# Mag_Read_STM_OUT.net
KiCad netlist of a schematic drawn in EAGLE
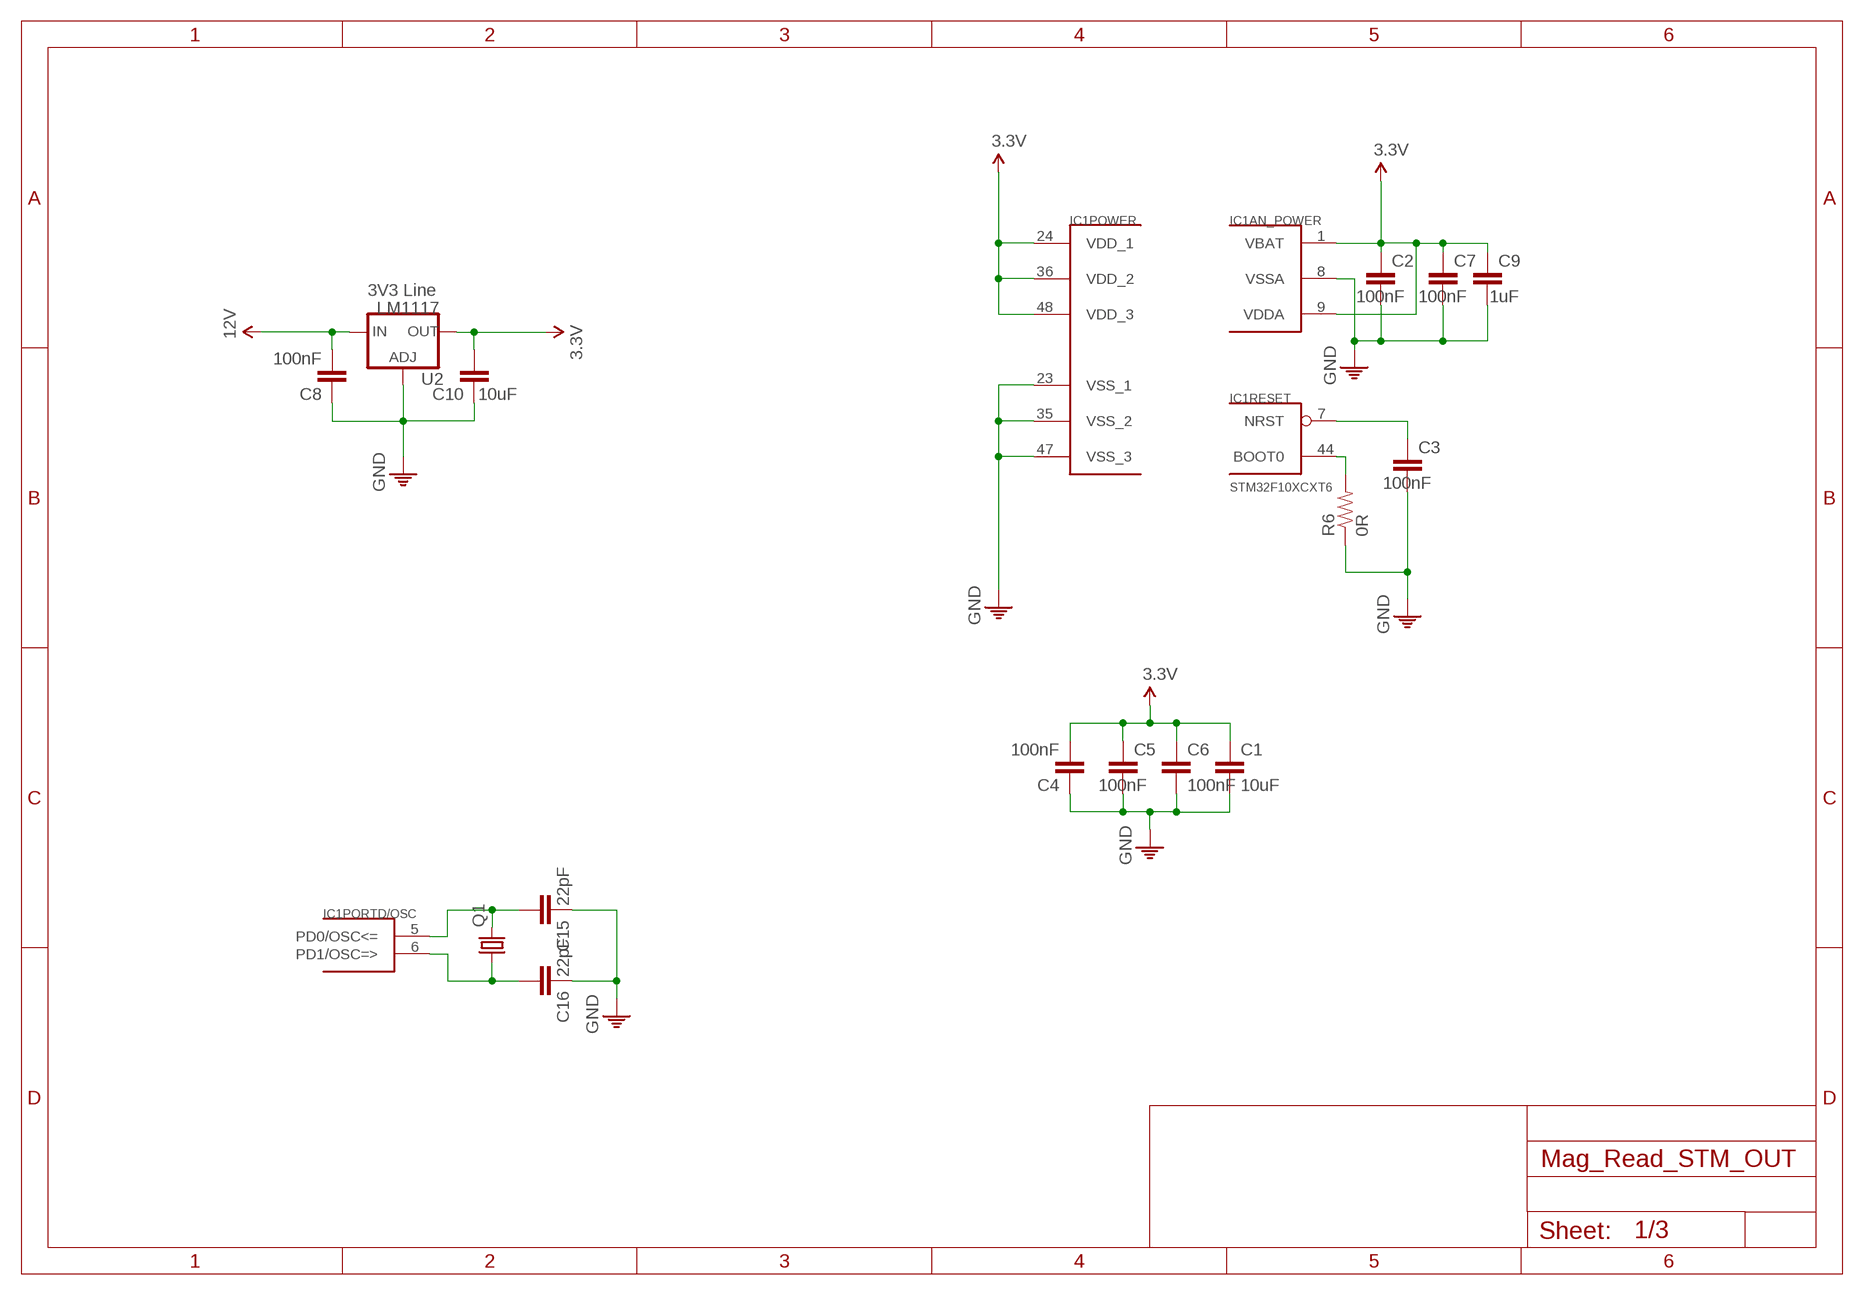
[diagram p0: schematic, sheet 1]
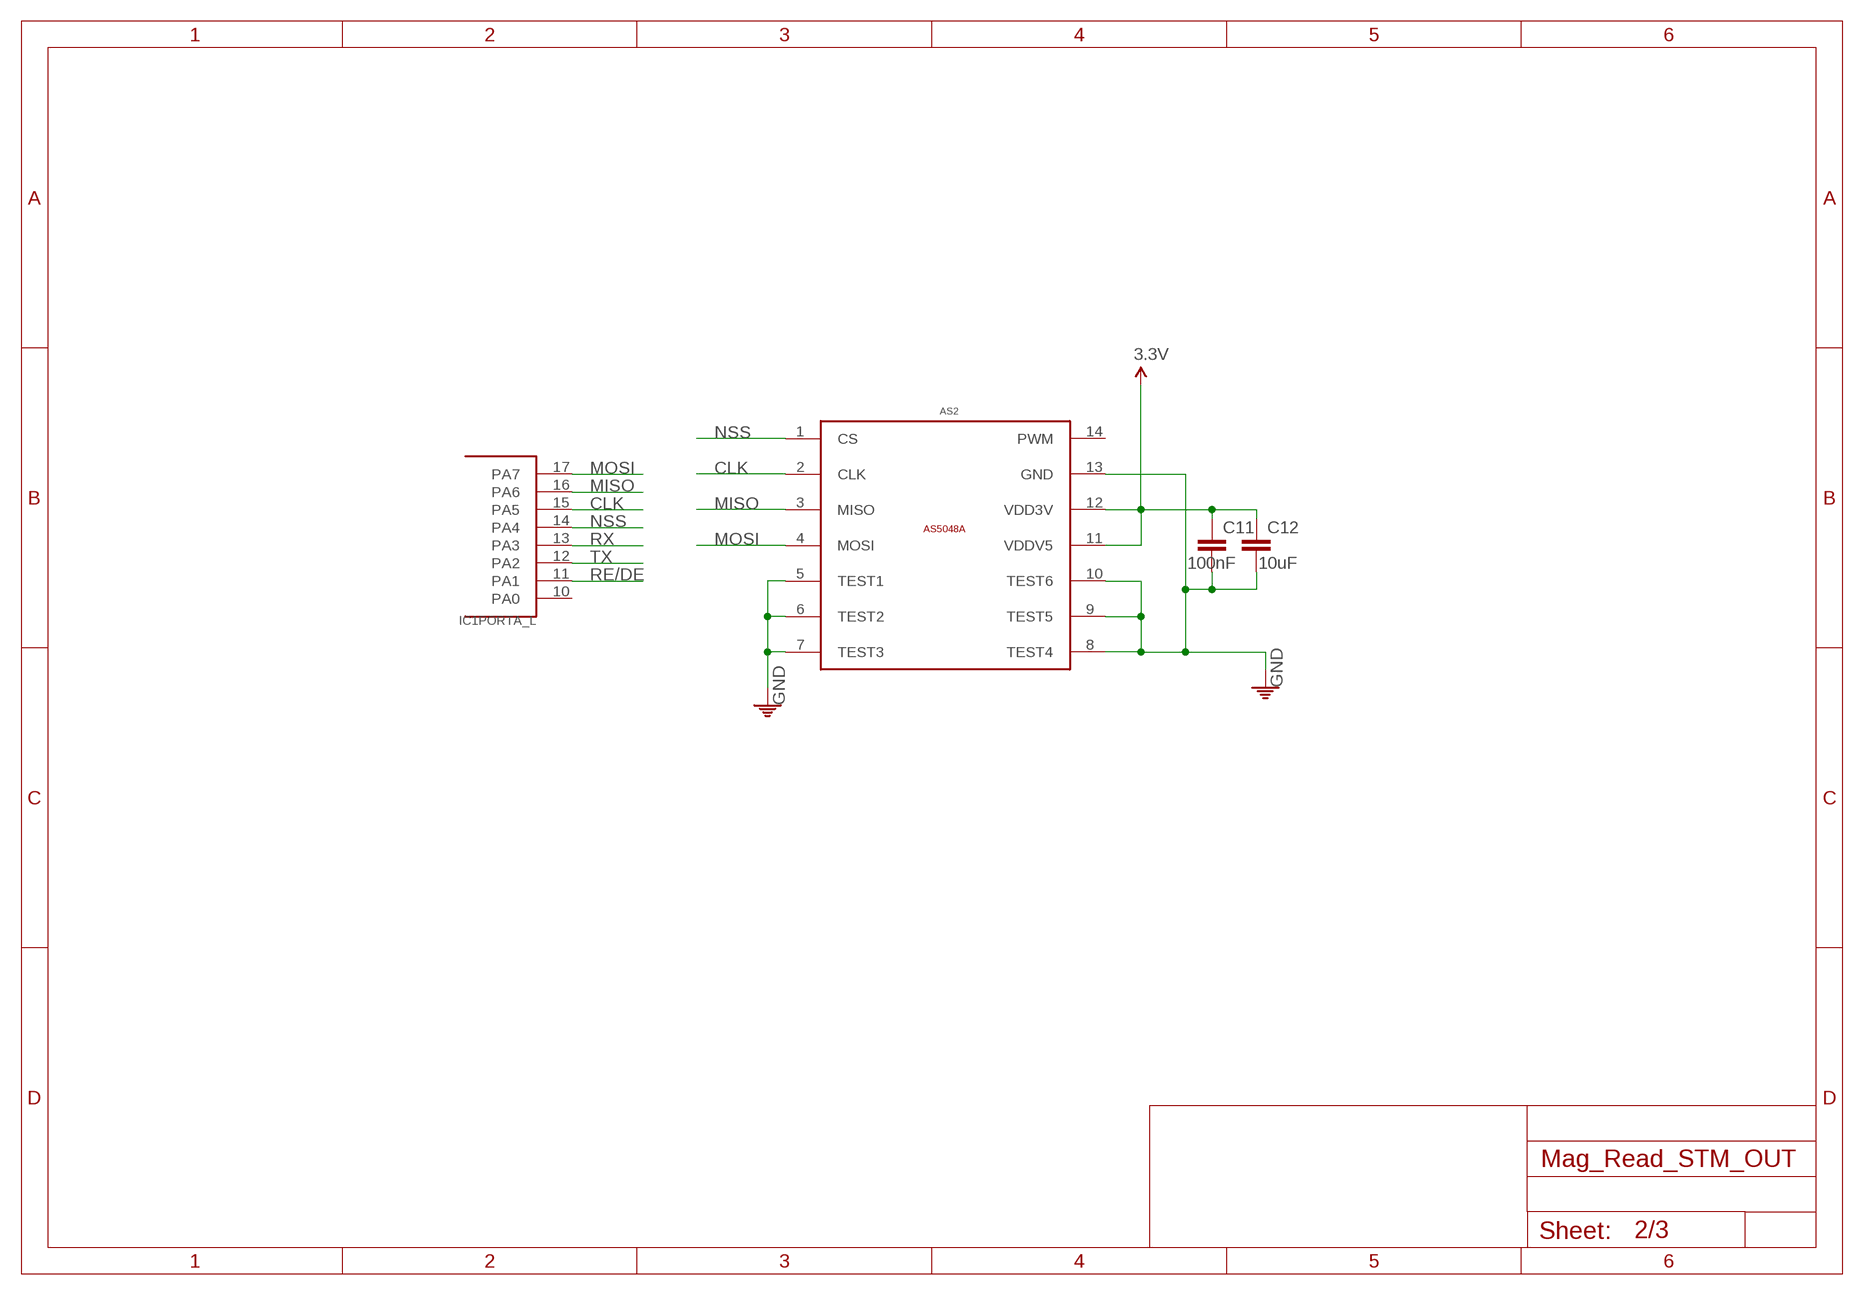
[diagram p1: schematic, sheet 2]
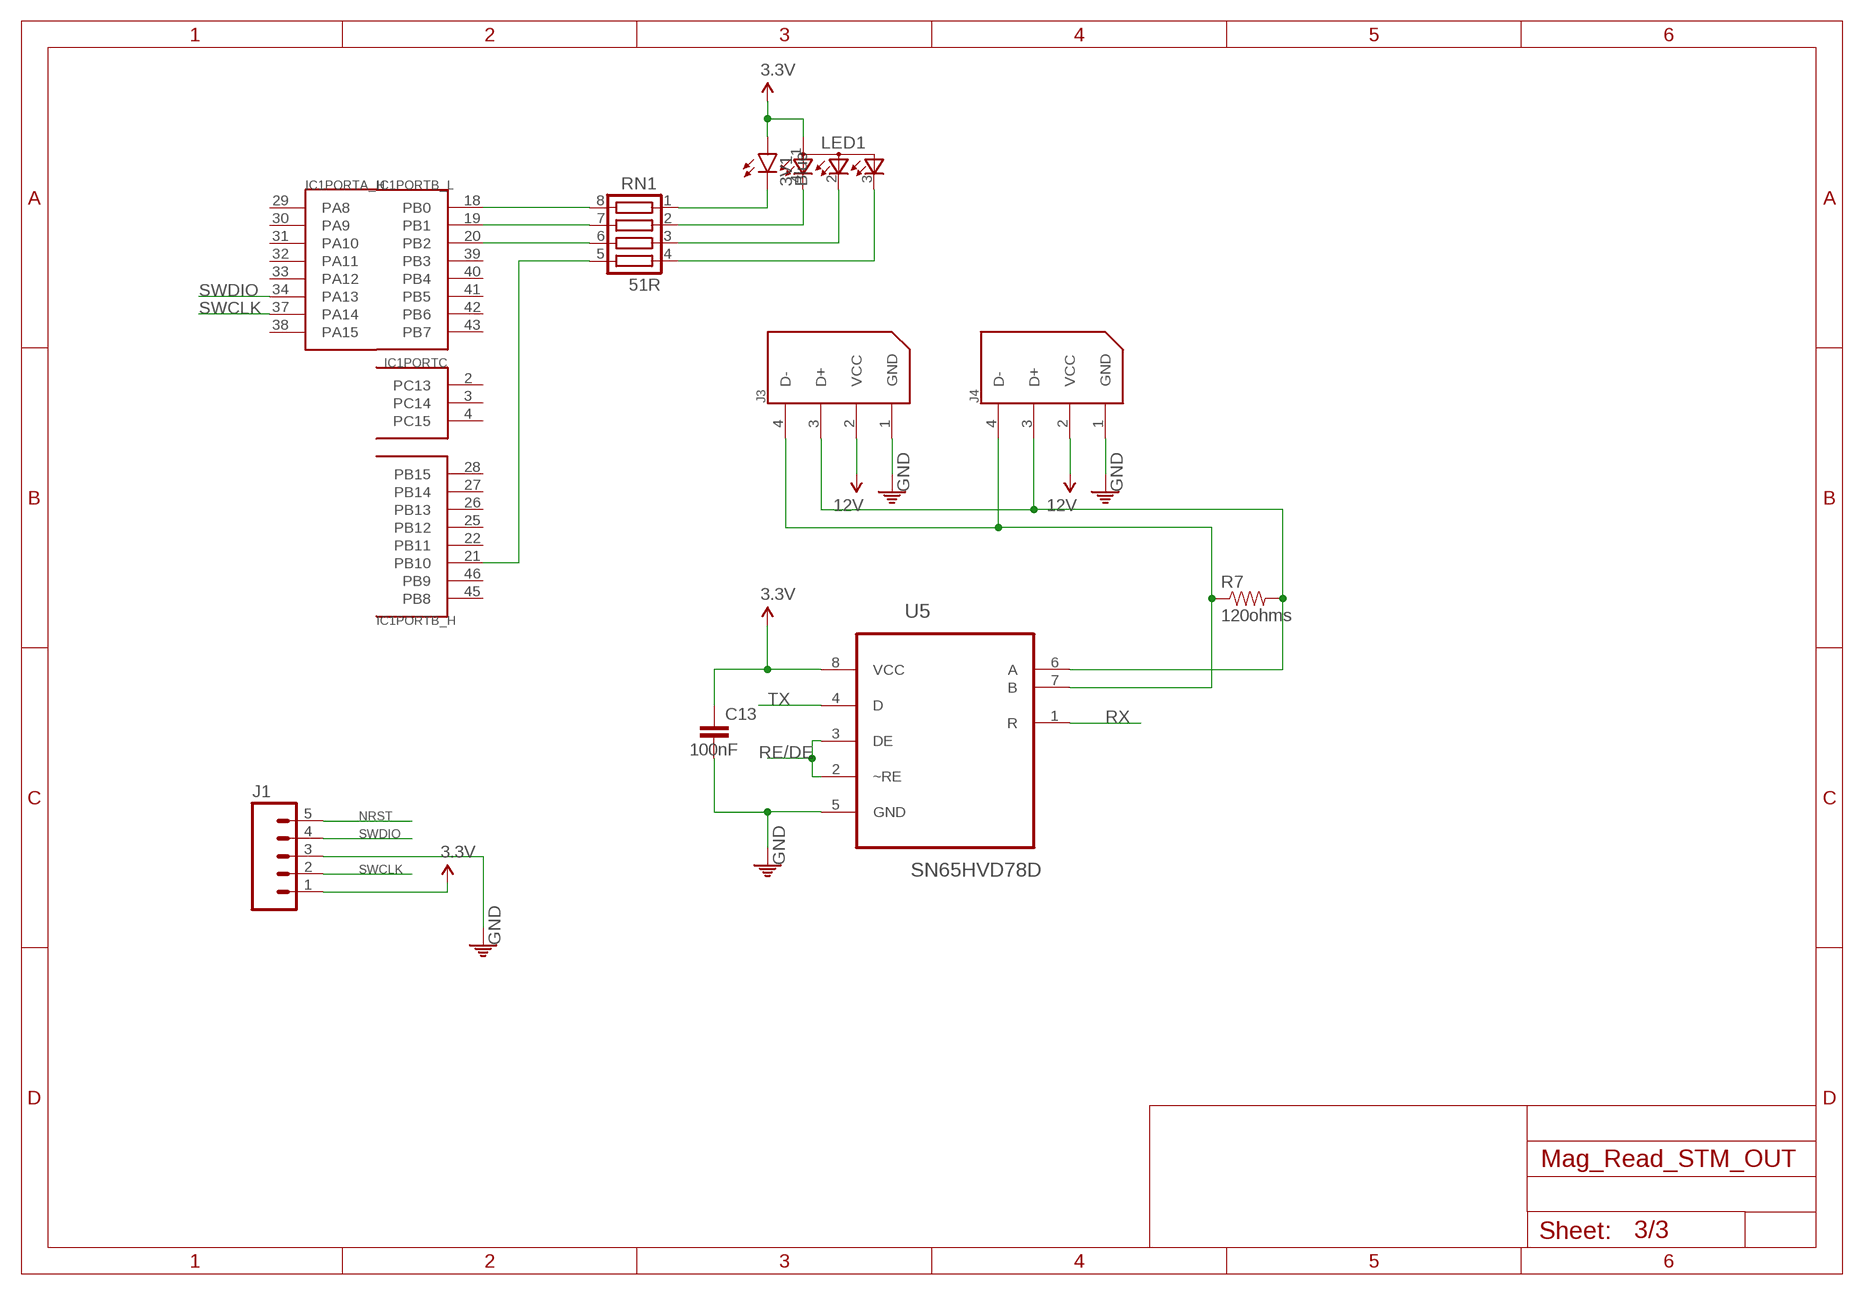
[diagram p2: schematic, sheet 3]

(export (version "E")
  (design (tool "Eeschema 10.0.6"))
  (components
    (comp (ref "C1")
      (value "10uF")
      (footprint "eagle-import:C0603")
      (libsource (lib "eagle-import") (part "C-EUC0603"))
    )
    (comp (ref "C2")
      (value "100nF")
      (footprint "eagle-import:C0603")
      (libsource (lib "eagle-import") (part "C-EUC0603"))
    )
    (comp (ref "C3")
      (value "100nF")
      (footprint "eagle-import:C0603")
      (libsource (lib "eagle-import") (part "C-EUC0603"))
    )
    (comp (ref "C4")
      (value "100nF")
      (footprint "eagle-import:C0603")
      (libsource (lib "eagle-import") (part "C-EUC0603"))
    )
    (comp (ref "C5")
      (value "100nF")
      (footprint "eagle-import:C0603")
      (libsource (lib "eagle-import") (part "C-EUC0603"))
    )
    (comp (ref "C6")
      (value "100nF")
      (footprint "eagle-import:C0603")
      (libsource (lib "eagle-import") (part "C-EUC0603"))
    )
    (comp (ref "C7")
      (value "100nF")
      (footprint "eagle-import:C0603")
      (libsource (lib "eagle-import") (part "C-EUC0603"))
    )
    (comp (ref "C8")
      (value "100nF")
      (footprint "eagle-import:C0603")
      (libsource (lib "eagle-import") (part "C-EUC0603"))
    )
    (comp (ref "C9")
      (value "1uF")
      (footprint "eagle-import:C0603")
      (libsource (lib "eagle-import") (part "C-EUC0603"))
    )
    (comp (ref "C10")
      (value "10uF")
      (footprint "eagle-import:C0603")
      (libsource (lib "eagle-import") (part "C-EUC0603"))
    )
    (comp (ref "C15")
      (value "22pF")
      (footprint "eagle-import:C0603")
      (libsource (lib "eagle-import") (part "C-EUC0603"))
    )
    (comp (ref "C16")
      (value "22pF")
      (footprint "eagle-import:C0603")
      (libsource (lib "eagle-import") (part "C-EUC0603"))
    )
    (comp (ref "IC1")
      (value "STM32F10XCXT6")
      (footprint "eagle-import:TQFP48")
      (libsource (lib "eagle-import") (part "STM32F10XCXT6"))
    )
    (comp (ref "Q1")
      (value "CRYSTALCTS406")
      (footprint "eagle-import:CTS406")
      (libsource (lib "eagle-import") (part "CRYSTALCTS406"))
    )
    (comp (ref "R6")
      (value "0R")
      (footprint "eagle-import:0603-RES")
      (libsource (lib "eagle-import") (part "RESISTOR0603-RES"))
    )
    (comp (ref "U2")
      (value "LM1117")
      (footprint "eagle-import:SOT223")
      (libsource (lib "eagle-import") (part "V_REG_317SMD"))
    )
    (comp (ref "3V1")
      (value "Blue")
      (footprint "eagle-import:LED-0603")
      (libsource (lib "eagle-import") (part "LED0603"))
    )
    (comp (ref "C13")
      (value "100nF")
      (footprint "eagle-import:C0603")
      (libsource (lib "eagle-import") (part "C-EUC0603"))
    )
    (comp (ref "J1")
      (value "M05PTH")
      (footprint "eagle-import:1X05")
      (libsource (lib "eagle-import") (part "M05PTH"))
    )
    (comp (ref "J3")
      (value "22-03-5045")
      (footprint "eagle-import:5267-4")
      (libsource (lib "eagle-import") (part "22-03-5045"))
    )
    (comp (ref "J4")
      (value "22-03-5045")
      (footprint "eagle-import:5267-4")
      (libsource (lib "eagle-import") (part "22-03-5045"))
    )
    (comp (ref "LED1")
      (value "TOPLED-3")
      (footprint "eagle-import:P-LCC-4-3")
      (libsource (lib "eagle-import") (part "TOPLED-3"))
    )
    (comp (ref "R7")
      (value "120ohms")
      (footprint "eagle-import:0603-RES")
      (libsource (lib "eagle-import") (part "RESISTOR0603-RES"))
    )
    (comp (ref "RN1")
      (value "51R")
      (footprint "eagle-import:CAY10-XXXJ4")
      (libsource (lib "eagle-import") (part "CAY10-XXXJ"))
    )
    (comp (ref "U5")
      (value "SN65HVD78D")
      (footprint "eagle-import:SOIC127P600X175-8N")
      (fields (field (name "MPN") "SN75176BD"))
      (libsource (lib "eagle-import") (part "SN75176BD"))
    )
    (comp (ref "AS2")
      (value "AS5048A_MAGNETIC_ROTARY_ENCODERTSSOP14")
      (footprint "eagle-import:AS5048A_14-TSSOP")
      (libsource (lib "eagle-import") (part "AS5048A_MAGNETIC_ROTARY_ENCODERTSSOP14"))
    )
    (comp (ref "C11")
      (value "100nF")
      (footprint "eagle-import:C0603")
      (libsource (lib "eagle-import") (part "C-EUC0603"))
    )
    (comp (ref "C12")
      (value "10uF")
      (footprint "eagle-import:C0603")
      (libsource (lib "eagle-import") (part "C-EUC0603"))
    )
  )
  (nets
    (net (code "1") (name "3.3V") (class "Default")
      (node (ref "3V1") (pin "A") (pinfunction "A_A") (pintype "passive"))
      (node (ref "AS2") (pin "11") (pinfunction "VDDV5_11") (pintype "bidirectional"))
      (node (ref "AS2") (pin "12") (pinfunction "VDD3V_12") (pintype "bidirectional"))
      (node (ref "C1") (pin "1") (pinfunction "1_1") (pintype "passive"))
      (node (ref "C10") (pin "2") (pinfunction "2_2") (pintype "passive"))
      (node (ref "C11") (pin "1") (pinfunction "1_1") (pintype "passive"))
      (node (ref "C12") (pin "1") (pinfunction "1_1") (pintype "passive"))
      (node (ref "C13") (pin "1") (pinfunction "1_1") (pintype "passive"))
      (node (ref "C2") (pin "1") (pinfunction "1_1") (pintype "passive"))
      (node (ref "C4") (pin "2") (pinfunction "2_2") (pintype "passive"))
      (node (ref "C5") (pin "1") (pinfunction "1_1") (pintype "passive"))
      (node (ref "C6") (pin "1") (pinfunction "1_1") (pintype "passive"))
      (node (ref "C7") (pin "1") (pinfunction "1_1") (pintype "passive"))
      (node (ref "C9") (pin "1") (pinfunction "1_1") (pintype "passive"))
      (node (ref "IC1") (pin "1") (pinfunction "VBAT_1") (pintype "power_in"))
      (node (ref "IC1") (pin "24") (pinfunction "VDD_1_24") (pintype "power_in"))
      (node (ref "IC1") (pin "36") (pinfunction "VDD_2_36") (pintype "power_in"))
      (node (ref "IC1") (pin "48") (pinfunction "VDD_3_48") (pintype "power_in"))
      (node (ref "IC1") (pin "9") (pinfunction "VDDA_9") (pintype "power_in"))
      (node (ref "J1") (pin "1") (pinfunction "1_1") (pintype "passive"))
      (node (ref "LED1") (pin "1") (pinfunction "A2_1") (pintype "passive"))
      (node (ref "U2") (pin "2") (pinfunction "OUT_2") (pintype "output"))
      (node (ref "U2") (pin "4") (pinfunction "OUT_4") (pintype "output"))
      (node (ref "U5") (pin "8") (pinfunction "VCC_8") (pintype "power_in"))
    )
    (net (code "2") (name "12V") (class "Default")
      (node (ref "C8") (pin "2") (pinfunction "2_2") (pintype "passive"))
      (node (ref "J3") (pin "2") (pinfunction "VCC_2") (pintype "bidirectional"))
      (node (ref "J4") (pin "2") (pinfunction "VCC_2") (pintype "bidirectional"))
      (node (ref "U2") (pin "3") (pinfunction "IN_3") (pintype "input"))
    )
    (net (code "3") (name "CLK") (class "Default")
      (node (ref "AS2") (pin "2") (pinfunction "CLK_2") (pintype "bidirectional"))
      (node (ref "IC1") (pin "15") (pinfunction "PA5_15") (pintype "bidirectional"))
    )
    (net (code "4") (name "GND") (class "Default")
      (node (ref "AS2") (pin "10") (pinfunction "TEST6_10") (pintype "bidirectional"))
      (node (ref "AS2") (pin "13") (pinfunction "GND_13") (pintype "bidirectional"))
      (node (ref "AS2") (pin "5") (pinfunction "TEST1_5") (pintype "bidirectional"))
      (node (ref "AS2") (pin "6") (pinfunction "TEST2_6") (pintype "bidirectional"))
      (node (ref "AS2") (pin "7") (pinfunction "TEST3_7") (pintype "bidirectional"))
      (node (ref "AS2") (pin "8") (pinfunction "TEST4_8") (pintype "bidirectional"))
      (node (ref "AS2") (pin "9") (pinfunction "TEST5_9") (pintype "bidirectional"))
      (node (ref "C1") (pin "2") (pinfunction "2_2") (pintype "passive"))
      (node (ref "C10") (pin "1") (pinfunction "1_1") (pintype "passive"))
      (node (ref "C11") (pin "2") (pinfunction "2_2") (pintype "passive"))
      (node (ref "C12") (pin "2") (pinfunction "2_2") (pintype "passive"))
      (node (ref "C13") (pin "2") (pinfunction "2_2") (pintype "passive"))
      (node (ref "C15") (pin "1") (pinfunction "1_1") (pintype "passive"))
      (node (ref "C16") (pin "1") (pinfunction "1_1") (pintype "passive"))
      (node (ref "C2") (pin "2") (pinfunction "2_2") (pintype "passive"))
      (node (ref "C3") (pin "2") (pinfunction "2_2") (pintype "passive"))
      (node (ref "C4") (pin "1") (pinfunction "1_1") (pintype "passive"))
      (node (ref "C5") (pin "2") (pinfunction "2_2") (pintype "passive"))
      (node (ref "C6") (pin "2") (pinfunction "2_2") (pintype "passive"))
      (node (ref "C7") (pin "2") (pinfunction "2_2") (pintype "passive"))
      (node (ref "C8") (pin "1") (pinfunction "1_1") (pintype "passive"))
      (node (ref "C9") (pin "2") (pinfunction "2_2") (pintype "passive"))
      (node (ref "IC1") (pin "23") (pinfunction "VSS_1_23") (pintype "power_in"))
      (node (ref "IC1") (pin "35") (pinfunction "VSS_2_35") (pintype "power_in"))
      (node (ref "IC1") (pin "47") (pinfunction "VSS_3_47") (pintype "power_in"))
      (node (ref "IC1") (pin "8") (pinfunction "VSSA_8") (pintype "power_in"))
      (node (ref "J1") (pin "3") (pinfunction "3_3") (pintype "passive"))
      (node (ref "J3") (pin "1") (pinfunction "GND_1") (pintype "bidirectional"))
      (node (ref "J4") (pin "1") (pinfunction "GND_1") (pintype "bidirectional"))
      (node (ref "R6") (pin "1") (pinfunction "1_1") (pintype "passive"))
      (node (ref "U2") (pin "1") (pinfunction "ADJ_1") (pintype "input"))
      (node (ref "U5") (pin "5") (pinfunction "GND_5") (pintype "passive"))
    )
    (net (code "5") (name "MISO") (class "Default")
      (node (ref "AS2") (pin "3") (pinfunction "MISO_3") (pintype "bidirectional"))
      (node (ref "IC1") (pin "16") (pinfunction "PA6_16") (pintype "bidirectional"))
    )
    (net (code "6") (name "MOSI") (class "Default")
      (node (ref "AS2") (pin "4") (pinfunction "MOSI_4") (pintype "bidirectional"))
      (node (ref "IC1") (pin "17") (pinfunction "PA7_17") (pintype "bidirectional"))
    )
    (net (code "7") (name "NRST") (class "Default")
      (node (ref "C3") (pin "1") (pinfunction "1_1") (pintype "passive"))
      (node (ref "IC1") (pin "7") (pinfunction "NRST_7") (pintype "input"))
      (node (ref "J1") (pin "5") (pinfunction "5_5") (pintype "passive"))
    )
    (net (code "8") (name "NSS") (class "Default")
      (node (ref "AS2") (pin "1") (pinfunction "CS_1") (pintype "bidirectional"))
      (node (ref "IC1") (pin "14") (pinfunction "PA4_14") (pintype "bidirectional"))
    )
    (net (code "9") (name "Net-(3V1-PadC)") (class "Default")
      (node (ref "3V1") (pin "C") (pinfunction "C_C") (pintype "passive"))
      (node (ref "RN1") (pin "1") (pinfunction "1_1") (pintype "passive"))
    )
    (net (code "10") (name "Net-(IC1D-PB10)") (class "Default")
      (node (ref "IC1") (pin "21") (pinfunction "PB10_21") (pintype "bidirectional"))
      (node (ref "RN1") (pin "5") (pinfunction "5_5") (pintype "passive"))
    )
    (net (code "11") (name "Net-(IC1E-PB0)") (class "Default")
      (node (ref "IC1") (pin "18") (pinfunction "PB0_18") (pintype "bidirectional"))
      (node (ref "RN1") (pin "8") (pinfunction "8_8") (pintype "passive"))
    )
    (net (code "12") (name "Net-(IC1E-PB1)") (class "Default")
      (node (ref "IC1") (pin "19") (pinfunction "PB1_19") (pintype "bidirectional"))
      (node (ref "RN1") (pin "7") (pinfunction "7_7") (pintype "passive"))
    )
    (net (code "13") (name "Net-(IC1E-PB2)") (class "Default")
      (node (ref "IC1") (pin "20") (pinfunction "PB2_20") (pintype "bidirectional"))
      (node (ref "RN1") (pin "6") (pinfunction "6_6") (pintype "passive"))
    )
    (net (code "14") (name "Net-(IC1G-PD0{slash}OSC<=)") (class "Default")
      (node (ref "C15") (pin "2") (pinfunction "2_2") (pintype "passive"))
      (node (ref "IC1") (pin "5") (pinfunction "PD0/OSC<=_5") (pintype "bidirectional"))
      (node (ref "Q1") (pin "3") (pinfunction "2_3") (pintype "passive"))
    )
    (net (code "15") (name "Net-(IC1G-PD1{slash}OSC=>)") (class "Default")
      (node (ref "C16") (pin "2") (pinfunction "2_2") (pintype "passive"))
      (node (ref "IC1") (pin "6") (pinfunction "PD1/OSC=>_6") (pintype "bidirectional"))
      (node (ref "Q1") (pin "1") (pinfunction "1_1") (pintype "passive"))
    )
    (net (code "16") (name "Net-(IC1I-BOOT0)") (class "Default")
      (node (ref "IC1") (pin "44") (pinfunction "BOOT0_44") (pintype "input"))
      (node (ref "R6") (pin "2") (pinfunction "2_2") (pintype "passive"))
    )
    (net (code "17") (name "Net-(J3-D+)") (class "Default")
      (node (ref "J3") (pin "3") (pinfunction "D+_3") (pintype "bidirectional"))
      (node (ref "J4") (pin "3") (pinfunction "D+_3") (pintype "bidirectional"))
      (node (ref "R7") (pin "2") (pinfunction "2_2") (pintype "passive"))
      (node (ref "U5") (pin "6") (pinfunction "A_6") (pintype "output"))
    )
    (net (code "18") (name "Net-(J3-D-)") (class "Default")
      (node (ref "J3") (pin "4") (pinfunction "D-_4") (pintype "bidirectional"))
      (node (ref "J4") (pin "4") (pinfunction "D-_4") (pintype "bidirectional"))
      (node (ref "R7") (pin "1") (pinfunction "1_1") (pintype "passive"))
      (node (ref "U5") (pin "7") (pinfunction "B_7") (pintype "output"))
    )
    (net (code "19") (name "Net-(LED1-CBLUE)") (class "Default")
      (node (ref "LED1") (pin "2") (pinfunction "CBLUE_2") (pintype "passive"))
      (node (ref "RN1") (pin "3") (pinfunction "3_3") (pintype "passive"))
    )
    (net (code "20") (name "Net-(LED1-CGREEN)") (class "Default")
      (node (ref "LED1") (pin "3") (pinfunction "CGREEN_3") (pintype "passive"))
      (node (ref "RN1") (pin "4") (pinfunction "4_4") (pintype "passive"))
    )
    (net (code "21") (name "Net-(LED1-CRED)") (class "Default")
      (node (ref "LED1") (pin "4") (pinfunction "CRED_4") (pintype "passive"))
      (node (ref "RN1") (pin "2") (pinfunction "2_2") (pintype "passive"))
    )
    (net (code "22") (name "RE{slash}DE") (class "Default")
      (node (ref "IC1") (pin "11") (pinfunction "PA1_11") (pintype "bidirectional"))
      (node (ref "U5") (pin "2") (pinfunction "~{RE}_2") (pintype "input"))
      (node (ref "U5") (pin "3") (pinfunction "DE_3") (pintype "input"))
    )
    (net (code "23") (name "RX") (class "Default")
      (node (ref "IC1") (pin "13") (pinfunction "PA3_13") (pintype "bidirectional"))
      (node (ref "U5") (pin "1") (pinfunction "R_1") (pintype "output"))
    )
    (net (code "24") (name "SWCLK") (class "Default")
      (node (ref "IC1") (pin "37") (pinfunction "PA14_37") (pintype "bidirectional"))
      (node (ref "J1") (pin "2") (pinfunction "2_2") (pintype "passive"))
    )
    (net (code "25") (name "SWDIO") (class "Default")
      (node (ref "IC1") (pin "34") (pinfunction "PA13_34") (pintype "bidirectional"))
      (node (ref "J1") (pin "4") (pinfunction "4_4") (pintype "passive"))
    )
    (net (code "26") (name "TX") (class "Default")
      (node (ref "IC1") (pin "12") (pinfunction "PA2_12") (pintype "bidirectional"))
      (node (ref "U5") (pin "4") (pinfunction "D_4") (pintype "input"))
    )
    (net (code "27") (name "unconnected-(AS2-PWM-Pad14)") (class "Default")
      (node (ref "AS2") (pin "14") (pinfunction "PWM_14") (pintype "bidirectional"))
    )
    (net (code "28") (name "unconnected-(IC1B-PA8-Pad29)") (class "Default")
      (node (ref "IC1") (pin "29") (pinfunction "PA8_29") (pintype "bidirectional"))
    )
    (net (code "29") (name "unconnected-(IC1B-PA9-Pad30)") (class "Default")
      (node (ref "IC1") (pin "30") (pinfunction "PA9_30") (pintype "bidirectional"))
    )
    (net (code "30") (name "unconnected-(IC1B-PA10-Pad31)") (class "Default")
      (node (ref "IC1") (pin "31") (pinfunction "PA10_31") (pintype "bidirectional"))
    )
    (net (code "31") (name "unconnected-(IC1B-PA11-Pad32)") (class "Default")
      (node (ref "IC1") (pin "32") (pinfunction "PA11_32") (pintype "bidirectional"))
    )
    (net (code "32") (name "unconnected-(IC1B-PA12-Pad33)") (class "Default")
      (node (ref "IC1") (pin "33") (pinfunction "PA12_33") (pintype "bidirectional"))
    )
    (net (code "33") (name "unconnected-(IC1B-PA15-Pad38)") (class "Default")
      (node (ref "IC1") (pin "38") (pinfunction "PA15_38") (pintype "bidirectional"))
    )
    (net (code "34") (name "unconnected-(IC1C-PA0-Pad10)") (class "Default")
      (node (ref "IC1") (pin "10") (pinfunction "PA0_10") (pintype "bidirectional"))
    )
    (net (code "35") (name "unconnected-(IC1D-PB8-Pad45)") (class "Default")
      (node (ref "IC1") (pin "45") (pinfunction "PB8_45") (pintype "bidirectional"))
    )
    (net (code "36") (name "unconnected-(IC1D-PB9-Pad46)") (class "Default")
      (node (ref "IC1") (pin "46") (pinfunction "PB9_46") (pintype "bidirectional"))
    )
    (net (code "37") (name "unconnected-(IC1D-PB11-Pad22)") (class "Default")
      (node (ref "IC1") (pin "22") (pinfunction "PB11_22") (pintype "bidirectional"))
    )
    (net (code "38") (name "unconnected-(IC1D-PB12-Pad25)") (class "Default")
      (node (ref "IC1") (pin "25") (pinfunction "PB12_25") (pintype "bidirectional"))
    )
    (net (code "39") (name "unconnected-(IC1D-PB13-Pad26)") (class "Default")
      (node (ref "IC1") (pin "26") (pinfunction "PB13_26") (pintype "bidirectional"))
    )
    (net (code "40") (name "unconnected-(IC1D-PB14-Pad27)") (class "Default")
      (node (ref "IC1") (pin "27") (pinfunction "PB14_27") (pintype "bidirectional"))
    )
    (net (code "41") (name "unconnected-(IC1D-PB15-Pad28)") (class "Default")
      (node (ref "IC1") (pin "28") (pinfunction "PB15_28") (pintype "bidirectional"))
    )
    (net (code "42") (name "unconnected-(IC1E-PB3-Pad39)") (class "Default")
      (node (ref "IC1") (pin "39") (pinfunction "PB3_39") (pintype "bidirectional"))
    )
    (net (code "43") (name "unconnected-(IC1E-PB4-Pad40)") (class "Default")
      (node (ref "IC1") (pin "40") (pinfunction "PB4_40") (pintype "bidirectional"))
    )
    (net (code "44") (name "unconnected-(IC1E-PB5-Pad41)") (class "Default")
      (node (ref "IC1") (pin "41") (pinfunction "PB5_41") (pintype "bidirectional"))
    )
    (net (code "45") (name "unconnected-(IC1E-PB6-Pad42)") (class "Default")
      (node (ref "IC1") (pin "42") (pinfunction "PB6_42") (pintype "bidirectional"))
    )
    (net (code "46") (name "unconnected-(IC1E-PB7-Pad43)") (class "Default")
      (node (ref "IC1") (pin "43") (pinfunction "PB7_43") (pintype "bidirectional"))
    )
    (net (code "47") (name "unconnected-(IC1F-PC13-Pad2)") (class "Default")
      (node (ref "IC1") (pin "2") (pinfunction "PC13_2") (pintype "bidirectional"))
    )
    (net (code "48") (name "unconnected-(IC1F-PC14-Pad3)") (class "Default")
      (node (ref "IC1") (pin "3") (pinfunction "PC14_3") (pintype "bidirectional"))
    )
    (net (code "49") (name "unconnected-(IC1F-PC15-Pad4)") (class "Default")
      (node (ref "IC1") (pin "4") (pinfunction "PC15_4") (pintype "bidirectional"))
    )
  )
)
